# Dynamixel_AX_adapter.net
KiCad netlist of a schematic drawn in Altium Designer
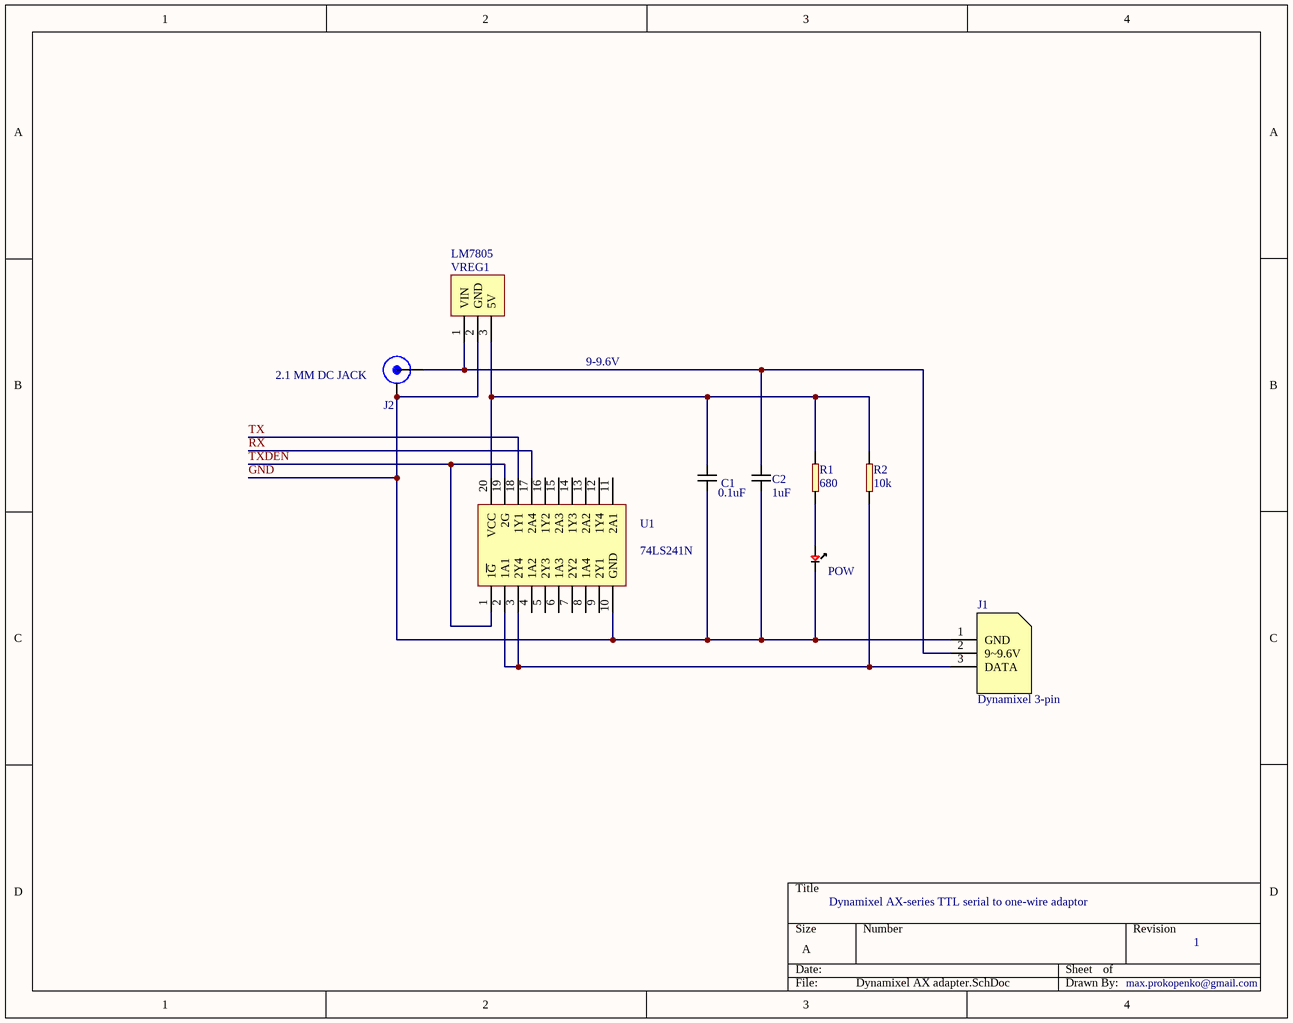
[diagram p0: Dynamixel AX adapter.SchDoc]

(export (version "E")
  (design (tool "Eeschema 10.0.6"))
  (components
    (comp (ref "C1")
      (value "C 0.1uF 25V")
      (footprint "0603")
      (fields (field (name "C") "0.1uF"))
      (libsource (lib "RLC") (part "C 0.1uF 25V"))
    )
    (comp (ref "C2")
      (value "C 1uF 25V")
      (footprint "0603")
      (fields (field (name "C") "1uF"))
      (libsource (lib "RLC") (part "C 1uF 25V"))
    )
    (comp (ref "J1")
      (value "Dynamixel 3-pin")
      (footprint "DYNAMIXEL 3-PIN")
      (libsource (lib "OpBots") (part "Dynamixel 3-pin"))
    )
    (comp (ref "J2")
      (value "2.1 MM DC JACK")
      (footprint "DC JACK 2.1MM SMT")
      (fields (field (name "VIN") "9-9.6V"))
      (libsource (lib "OpBots") (part "SMT 2.1MM DC JACK"))
    )
    (comp (ref "POW") (value "LEDG") (footprint "0805 - LED") (libsource (lib "OpBots") (part "LEDG")))
    (comp (ref "R1")
      (value "R 680")
      (footprint "0603")
      (fields (field (name "R") "680"))
      (libsource (lib "RLC") (part "R 680"))
    )
    (comp (ref "R2")
      (value "R 10k")
      (footprint "0603")
      (fields (field (name "R") "10k"))
      (libsource (lib "RLC") (part "R 10k"))
    )
    (comp (ref "U1") (value "74LS241N") (libsource (lib "OpBots") (part "74LS241N")))
    (comp (ref "VREG1") (value "LM7805") (libsource (lib "OpBots") (part "LM7805")))
  )
  (nets
    (net (code "1") (name "/GND") (class "Default")
      (node (ref "C1") (pin "2") (pintype "passive"))
      (node (ref "C2") (pin "2") (pintype "passive"))
      (node (ref "J1") (pin "1") (pinfunction "GND_1") (pintype "passive"))
      (node (ref "J2") (pin "2") (pinfunction "G_2") (pintype "passive"))
      (node (ref "POW") (pin "2") (pinfunction "K_2") (pintype "passive"))
      (node (ref "U1") (pin "10") (pinfunction "GND_10") (pintype "passive"))
      (node (ref "VREG1") (pin "2") (pinfunction "GND_2") (pintype "passive"))
    )
    (net (code "2") (name "/RX") (class "Default")
      (node (ref "U1") (pin "17") (pinfunction "2A4_17") (pintype "passive"))
    )
    (net (code "3") (name "/TX") (class "Default")
      (node (ref "U1") (pin "18") (pinfunction "1Y1_18") (pintype "passive"))
    )
    (net (code "4") (name "/TXDEN") (class "Default")
      (node (ref "U1") (pin "1") (pinfunction "1~{G}_1") (pintype "passive"))
      (node (ref "U1") (pin "19") (pinfunction "2G_19") (pintype "passive"))
    )
    (net (code "5") (name "Net-(J1-9~9.6V)") (class "Default")
      (node (ref "C2") (pin "1") (pintype "passive"))
      (node (ref "J1") (pin "2") (pinfunction "9~9.6V_2") (pintype "passive"))
      (node (ref "J2") (pin "1") (pinfunction "S_1") (pintype "passive"))
      (node (ref "VREG1") (pin "1") (pinfunction "VIN_1") (pintype "passive"))
    )
    (net (code "6") (name "Net-(J1-DATA)") (class "Default")
      (node (ref "J1") (pin "3") (pinfunction "DATA_3") (pintype "passive"))
      (node (ref "R2") (pin "2") (pintype "passive"))
      (node (ref "U1") (pin "2") (pinfunction "1A1_2") (pintype "passive"))
      (node (ref "U1") (pin "3") (pinfunction "2Y4_3") (pintype "passive"))
    )
    (net (code "7") (name "Net-(POW-A)") (class "Default")
      (node (ref "POW") (pin "1") (pinfunction "A_1") (pintype "passive"))
      (node (ref "R1") (pin "2") (pintype "passive"))
    )
    (net (code "8") (name "Net-(U1-VCC)") (class "Default")
      (node (ref "C1") (pin "1") (pintype "passive"))
      (node (ref "R1") (pin "1") (pintype "passive"))
      (node (ref "R2") (pin "1") (pintype "passive"))
      (node (ref "U1") (pin "20") (pinfunction "VCC_20") (pintype "passive"))
      (node (ref "VREG1") (pin "3") (pinfunction "5V_3") (pintype "passive"))
    )
    (net (code "9") (name "unconnected-(U1-1A2-Pad4)") (class "Default")
      (node (ref "U1") (pin "4") (pinfunction "1A2_4") (pintype "passive"))
    )
    (net (code "10") (name "unconnected-(U1-1A3-Pad6)") (class "Default")
      (node (ref "U1") (pin "6") (pinfunction "1A3_6") (pintype "passive"))
    )
    (net (code "11") (name "unconnected-(U1-1A4-Pad8)") (class "Default")
      (node (ref "U1") (pin "8") (pinfunction "1A4_8") (pintype "passive"))
    )
    (net (code "12") (name "unconnected-(U1-1Y2-Pad16)") (class "Default")
      (node (ref "U1") (pin "16") (pinfunction "1Y2_16") (pintype "passive"))
    )
    (net (code "13") (name "unconnected-(U1-1Y3-Pad14)") (class "Default")
      (node (ref "U1") (pin "14") (pinfunction "1Y3_14") (pintype "passive"))
    )
    (net (code "14") (name "unconnected-(U1-1Y4-Pad12)") (class "Default")
      (node (ref "U1") (pin "12") (pinfunction "1Y4_12") (pintype "passive"))
    )
    (net (code "15") (name "unconnected-(U1-2A1-Pad11)") (class "Default")
      (node (ref "U1") (pin "11") (pinfunction "2A1_11") (pintype "passive"))
    )
    (net (code "16") (name "unconnected-(U1-2A2-Pad13)") (class "Default")
      (node (ref "U1") (pin "13") (pinfunction "2A2_13") (pintype "passive"))
    )
    (net (code "17") (name "unconnected-(U1-2A3-Pad15)") (class "Default")
      (node (ref "U1") (pin "15") (pinfunction "2A3_15") (pintype "passive"))
    )
    (net (code "18") (name "unconnected-(U1-2Y1-Pad9)") (class "Default")
      (node (ref "U1") (pin "9") (pinfunction "2Y1_9") (pintype "passive"))
    )
    (net (code "19") (name "unconnected-(U1-2Y2-Pad7)") (class "Default")
      (node (ref "U1") (pin "7") (pinfunction "2Y2_7") (pintype "passive"))
    )
    (net (code "20") (name "unconnected-(U1-2Y3-Pad5)") (class "Default")
      (node (ref "U1") (pin "5") (pinfunction "2Y3_5") (pintype "passive"))
    )
  )
)
